# esquematico_pic_esp8266.net
KiCad netlist of a schematic drawn in EAGLE
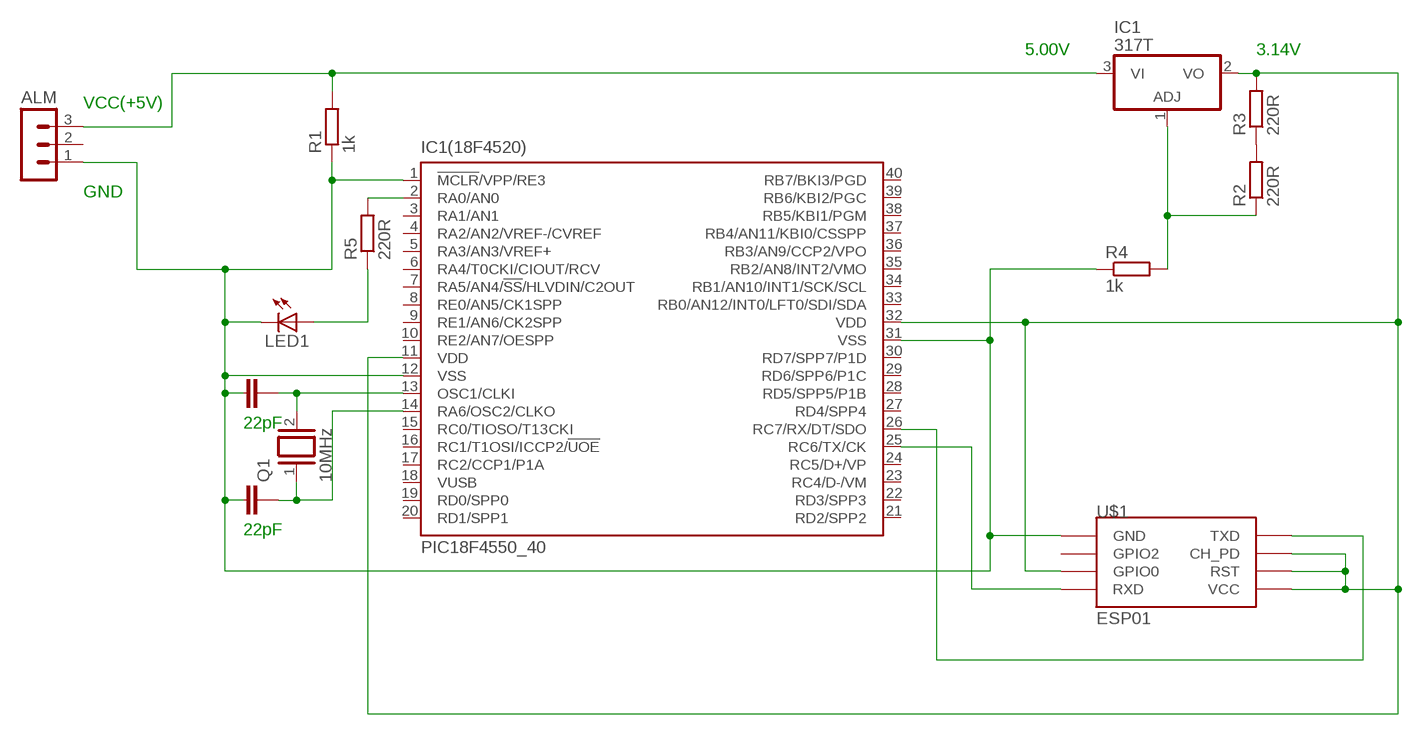
[diagram p0: schematic, sheet 1]

(export (version "E")
  (design (tool "Eeschema 10.0.6"))
  (components
    (comp (ref "ALM")
      (value "MA03-1")
      (footprint "eagle-import:MA03-1")
      (libsource (lib "eagle-import") (part "MA03-1"))
    )
    (comp (ref "IC1")
      (value "317T")
      (footprint "eagle-import:TO220H")
      (libsource (lib "eagle-import") (part "317T"))
    )
    (comp (ref "IC1(18F4520)")
      (value "PIC18F4550_40")
      (footprint "eagle-import:DIL40")
      (fields (field (name "MF") "MICROCHIP") (field (name "MPN") "PIC18F4550-I/P"))
      (libsource (lib "eagle-import") (part "PIC18F4_40550"))
    )
    (comp (ref "LED1")
      (value "LED3MM")
      (footprint "eagle-import:LED3MM")
      (libsource (lib "eagle-import") (part "LED3MM"))
    )
    (comp (ref "Q1")
      (value "10MHz")
      (footprint "eagle-import:Q")
      (libsource (lib "eagle-import") (part "XTAL"))
    )
    (comp (ref "R1")
      (value "1k")
      (footprint "eagle-import:0207_10")
      (libsource (lib "eagle-import") (part "R-EU_0207/10"))
    )
    (comp (ref "R2")
      (value "220R")
      (footprint "eagle-import:0207_10")
      (libsource (lib "eagle-import") (part "R-EU_0207/10"))
    )
    (comp (ref "R3")
      (value "220R")
      (footprint "eagle-import:0207_10")
      (libsource (lib "eagle-import") (part "R-EU_0207/10"))
    )
    (comp (ref "R4")
      (value "1k")
      (footprint "eagle-import:0207_10")
      (libsource (lib "eagle-import") (part "R-EU_0207/10"))
    )
    (comp (ref "R5")
      (value "220R")
      (footprint "eagle-import:0207_10")
      (libsource (lib "eagle-import") (part "R-EU_0207/10"))
    )
    (comp (ref "U$1")
      (value "ESP01")
      (footprint "eagle-import:ESP01")
      (libsource (lib "eagle-import") (part "ESP01"))
    )
  )
  (nets
    (net (code "1") (name "Net-(IC1(18F4520)-OSC1{slash}CLKI)") (class "Default")
      (node (ref "IC1(18F4520)") (pin "13") (pinfunction "OSC1/CLKI_13") (pintype "input"))
      (node (ref "Q1") (pin "2") (pinfunction "2_2") (pintype "passive"))
    )
    (net (code "2") (name "Net-(IC1(18F4520)-RA0{slash}AN0)") (class "Default")
      (node (ref "IC1(18F4520)") (pin "2") (pinfunction "RA0/AN0_2") (pintype "bidirectional"))
      (node (ref "R5") (pin "2") (pinfunction "2_2") (pintype "passive"))
    )
    (net (code "3") (name "Net-(IC1(18F4520)-RA6{slash}OSC2{slash}CLKO)") (class "Default")
      (node (ref "IC1(18F4520)") (pin "14") (pinfunction "RA6/OSC2/CLKO_14") (pintype "output"))
      (node (ref "Q1") (pin "1") (pinfunction "1_1") (pintype "passive"))
    )
    (net (code "4") (name "Net-(IC1(18F4520)-RC6{slash}TX{slash}CK)") (class "Default")
      (node (ref "IC1(18F4520)") (pin "25") (pinfunction "RC6/TX/CK_25") (pintype "bidirectional"))
      (node (ref "U$1") (pin "RX") (pinfunction "RXD_RX") (pintype "bidirectional"))
    )
    (net (code "5") (name "Net-(IC1(18F4520)-RC7{slash}RX{slash}DT{slash}SDO)") (class "Default")
      (node (ref "IC1(18F4520)") (pin "26") (pinfunction "RC7/RX/DT/SDO_26") (pintype "bidirectional"))
      (node (ref "U$1") (pin "TX") (pinfunction "TXD_TX") (pintype "bidirectional"))
    )
    (net (code "6") (name "Net-(IC1(18F4520)-~{MCLR}{slash}VPP{slash}RE3)") (class "Default")
      (node (ref "ALM") (pin "1") (pinfunction "1_1") (pintype "passive"))
      (node (ref "IC1(18F4520)") (pin "1") (pinfunction "~{MCLR}/VPP/RE3_1") (pintype "input"))
      (node (ref "IC1(18F4520)") (pin "12") (pinfunction "VSS_12") (pintype "power_in"))
      (node (ref "IC1(18F4520)") (pin "31") (pinfunction "VSS_31") (pintype "power_in"))
      (node (ref "LED1") (pin "K") (pinfunction "C_K") (pintype "passive"))
      (node (ref "R1") (pin "1") (pinfunction "1_1") (pintype "passive"))
      (node (ref "R4") (pin "1") (pinfunction "1_1") (pintype "passive"))
      (node (ref "U$1") (pin "GND") (pinfunction "GND_GND") (pintype "bidirectional"))
    )
    (net (code "7") (name "Net-(IC1-ADJ)") (class "Default")
      (node (ref "IC1") (pin "1") (pinfunction "ADJ_1") (pintype "input"))
      (node (ref "R2") (pin "1") (pinfunction "1_1") (pintype "passive"))
      (node (ref "R4") (pin "2") (pinfunction "2_2") (pintype "passive"))
    )
    (net (code "8") (name "Net-(IC1-VI)") (class "Default")
      (node (ref "ALM") (pin "3") (pinfunction "3_3") (pintype "passive"))
      (node (ref "IC1") (pin "3") (pinfunction "VI_3") (pintype "input"))
      (node (ref "R1") (pin "2") (pinfunction "2_2") (pintype "passive"))
    )
    (net (code "9") (name "Net-(IC1-VO)") (class "Default")
      (node (ref "IC1") (pin "2") (pinfunction "VO_2") (pintype "passive"))
      (node (ref "IC1(18F4520)") (pin "11") (pinfunction "VDD_11") (pintype "power_in"))
      (node (ref "IC1(18F4520)") (pin "32") (pinfunction "VDD_32") (pintype "power_in"))
      (node (ref "R3") (pin "2") (pinfunction "2_2") (pintype "passive"))
      (node (ref "U$1") (pin "CH_PD") (pinfunction "CH_PD_CH_PD") (pintype "bidirectional"))
      (node (ref "U$1") (pin "GPIO0") (pinfunction "GPIO0_GPIO0") (pintype "bidirectional"))
      (node (ref "U$1") (pin "RST") (pinfunction "RST_RST") (pintype "bidirectional"))
      (node (ref "U$1") (pin "VCC") (pinfunction "VCC_VCC") (pintype "bidirectional"))
    )
    (net (code "10") (name "Net-(LED1-PadA)") (class "Default")
      (node (ref "LED1") (pin "A") (pinfunction "A_A") (pintype "passive"))
      (node (ref "R5") (pin "1") (pinfunction "1_1") (pintype "passive"))
    )
    (net (code "11") (name "Net-(R2-Pad2)") (class "Default")
      (node (ref "R2") (pin "2") (pinfunction "2_2") (pintype "passive"))
      (node (ref "R3") (pin "1") (pinfunction "1_1") (pintype "passive"))
    )
    (net (code "12") (name "unconnected-(ALM-Pad2)") (class "Default")
      (node (ref "ALM") (pin "2") (pinfunction "2_2") (pintype "passive"))
    )
    (net (code "13") (name "unconnected-(IC1(18F4520)-RA1{slash}AN1-Pad3)") (class "Default")
      (node (ref "IC1(18F4520)") (pin "3") (pinfunction "RA1/AN1_3") (pintype "bidirectional"))
    )
    (net (code "14") (name "unconnected-(IC1(18F4520)-RA2{slash}AN2{slash}VREF-{slash}CVREF-Pad4)") (class "Default")
      (node (ref "IC1(18F4520)") (pin "4") (pinfunction "RA2/AN2/VREF-/CVREF_4") (pintype "bidirectional"))
    )
    (net (code "15") (name "unconnected-(IC1(18F4520)-RA3{slash}AN3{slash}VREF+-Pad5)") (class "Default")
      (node (ref "IC1(18F4520)") (pin "5") (pinfunction "RA3/AN3/VREF+_5") (pintype "bidirectional"))
    )
    (net (code "16") (name "unconnected-(IC1(18F4520)-RA4{slash}T0CKI{slash}CIOUT{slash}RCV-Pad6)") (class "Default")
      (node (ref "IC1(18F4520)") (pin "6") (pinfunction "RA4/T0CKI/CIOUT/RCV_6") (pintype "bidirectional"))
    )
    (net (code "17") (name "unconnected-(IC1(18F4520)-RA5{slash}AN4{slash}~{SS}{slash}HLVDIN{slash}C2OUT-Pad7)") (class "Default")
      (node (ref "IC1(18F4520)") (pin "7") (pinfunction "RA5/AN4/~{SS}/HLVDIN/C2OUT_7") (pintype "bidirectional"))
    )
    (net (code "18") (name "unconnected-(IC1(18F4520)-RB0{slash}AN12{slash}INT0{slash}LFT0{slash}SDI{slash}SDA-Pad33)") (class "Default")
      (node (ref "IC1(18F4520)") (pin "33") (pinfunction "RB0/AN12/INT0/LFT0/SDI/SDA_33") (pintype "bidirectional"))
    )
    (net (code "19") (name "unconnected-(IC1(18F4520)-RB1{slash}AN10{slash}INT1{slash}SCK{slash}SCL-Pad34)") (class "Default")
      (node (ref "IC1(18F4520)") (pin "34") (pinfunction "RB1/AN10/INT1/SCK/SCL_34") (pintype "bidirectional"))
    )
    (net (code "20") (name "unconnected-(IC1(18F4520)-RB2{slash}AN8{slash}INT2{slash}VMO-Pad35)") (class "Default")
      (node (ref "IC1(18F4520)") (pin "35") (pinfunction "RB2/AN8/INT2/VMO_35") (pintype "bidirectional"))
    )
    (net (code "21") (name "unconnected-(IC1(18F4520)-RB3{slash}AN9{slash}CCP2{slash}VPO-Pad36)") (class "Default")
      (node (ref "IC1(18F4520)") (pin "36") (pinfunction "RB3/AN9/CCP2/VPO_36") (pintype "bidirectional"))
    )
    (net (code "22") (name "unconnected-(IC1(18F4520)-RB4{slash}AN11{slash}KBI0{slash}CSSPP-Pad37)") (class "Default")
      (node (ref "IC1(18F4520)") (pin "37") (pinfunction "RB4/AN11/KBI0/CSSPP_37") (pintype "bidirectional"))
    )
    (net (code "23") (name "unconnected-(IC1(18F4520)-RB5{slash}KBI1{slash}PGM-Pad38)") (class "Default")
      (node (ref "IC1(18F4520)") (pin "38") (pinfunction "RB5/KBI1/PGM_38") (pintype "bidirectional"))
    )
    (net (code "24") (name "unconnected-(IC1(18F4520)-RB6{slash}KBI2{slash}PGC-Pad39)") (class "Default")
      (node (ref "IC1(18F4520)") (pin "39") (pinfunction "RB6/KBI2/PGC_39") (pintype "bidirectional"))
    )
    (net (code "25") (name "unconnected-(IC1(18F4520)-RB7{slash}BKI3{slash}PGD-Pad40)") (class "Default")
      (node (ref "IC1(18F4520)") (pin "40") (pinfunction "RB7/BKI3/PGD_40") (pintype "bidirectional"))
    )
    (net (code "26") (name "unconnected-(IC1(18F4520)-RC0{slash}TIOSO{slash}T13CKI-Pad15)") (class "Default")
      (node (ref "IC1(18F4520)") (pin "15") (pinfunction "RC0/TIOSO/T13CKI_15") (pintype "bidirectional"))
    )
    (net (code "27") (name "unconnected-(IC1(18F4520)-RC1{slash}T1OSI{slash}ICCP2{slash}~{UOE}-Pad16)") (class "Default")
      (node (ref "IC1(18F4520)") (pin "16") (pinfunction "RC1/T1OSI/ICCP2/~{UOE}_16") (pintype "bidirectional"))
    )
    (net (code "28") (name "unconnected-(IC1(18F4520)-RC2{slash}CCP1{slash}P1A-Pad17)") (class "Default")
      (node (ref "IC1(18F4520)") (pin "17") (pinfunction "RC2/CCP1/P1A_17") (pintype "bidirectional"))
    )
    (net (code "29") (name "unconnected-(IC1(18F4520)-RC4{slash}D-{slash}VM-Pad23)") (class "Default")
      (node (ref "IC1(18F4520)") (pin "23") (pinfunction "RC4/D-/VM_23") (pintype "bidirectional"))
    )
    (net (code "30") (name "unconnected-(IC1(18F4520)-RC5{slash}D+{slash}VP-Pad24)") (class "Default")
      (node (ref "IC1(18F4520)") (pin "24") (pinfunction "RC5/D+/VP_24") (pintype "bidirectional"))
    )
    (net (code "31") (name "unconnected-(IC1(18F4520)-RD0{slash}SPP0-Pad19)") (class "Default")
      (node (ref "IC1(18F4520)") (pin "19") (pinfunction "RD0/SPP0_19") (pintype "bidirectional"))
    )
    (net (code "32") (name "unconnected-(IC1(18F4520)-RD1{slash}SPP1-Pad20)") (class "Default")
      (node (ref "IC1(18F4520)") (pin "20") (pinfunction "RD1/SPP1_20") (pintype "bidirectional"))
    )
    (net (code "33") (name "unconnected-(IC1(18F4520)-RD2{slash}SPP2-Pad21)") (class "Default")
      (node (ref "IC1(18F4520)") (pin "21") (pinfunction "RD2/SPP2_21") (pintype "bidirectional"))
    )
    (net (code "34") (name "unconnected-(IC1(18F4520)-RD3{slash}SPP3-Pad22)") (class "Default")
      (node (ref "IC1(18F4520)") (pin "22") (pinfunction "RD3/SPP3_22") (pintype "bidirectional"))
    )
    (net (code "35") (name "unconnected-(IC1(18F4520)-RD4{slash}SPP4-Pad27)") (class "Default")
      (node (ref "IC1(18F4520)") (pin "27") (pinfunction "RD4/SPP4_27") (pintype "bidirectional"))
    )
    (net (code "36") (name "unconnected-(IC1(18F4520)-RD5{slash}SPP5{slash}P1B-Pad28)") (class "Default")
      (node (ref "IC1(18F4520)") (pin "28") (pinfunction "RD5/SPP5/P1B_28") (pintype "bidirectional"))
    )
    (net (code "37") (name "unconnected-(IC1(18F4520)-RD6{slash}SPP6{slash}P1C-Pad29)") (class "Default")
      (node (ref "IC1(18F4520)") (pin "29") (pinfunction "RD6/SPP6/P1C_29") (pintype "bidirectional"))
    )
    (net (code "38") (name "unconnected-(IC1(18F4520)-RD7{slash}SPP7{slash}P1D-Pad30)") (class "Default")
      (node (ref "IC1(18F4520)") (pin "30") (pinfunction "RD7/SPP7/P1D_30") (pintype "bidirectional"))
    )
    (net (code "39") (name "unconnected-(IC1(18F4520)-RE0{slash}AN5{slash}CK1SPP-Pad8)") (class "Default")
      (node (ref "IC1(18F4520)") (pin "8") (pinfunction "RE0/AN5/CK1SPP_8") (pintype "bidirectional"))
    )
    (net (code "40") (name "unconnected-(IC1(18F4520)-RE1{slash}AN6{slash}CK2SPP-Pad9)") (class "Default")
      (node (ref "IC1(18F4520)") (pin "9") (pinfunction "RE1/AN6/CK2SPP_9") (pintype "bidirectional"))
    )
    (net (code "41") (name "unconnected-(IC1(18F4520)-RE2{slash}AN7{slash}OESPP-Pad10)") (class "Default")
      (node (ref "IC1(18F4520)") (pin "10") (pinfunction "RE2/AN7/OESPP_10") (pintype "bidirectional"))
    )
    (net (code "42") (name "unconnected-(IC1(18F4520)-VUSB-Pad18)") (class "Default")
      (node (ref "IC1(18F4520)") (pin "18") (pinfunction "VUSB_18") (pintype "bidirectional"))
    )
    (net (code "43") (name "unconnected-(U$1-PadGPIO2)") (class "Default")
      (node (ref "U$1") (pin "GPIO2") (pinfunction "GPIO2_GPIO2") (pintype "bidirectional"))
    )
  )
)
